# blink1mk3_005t6_5050_4l_usbc.net
KiCad netlist of a schematic drawn in EAGLE
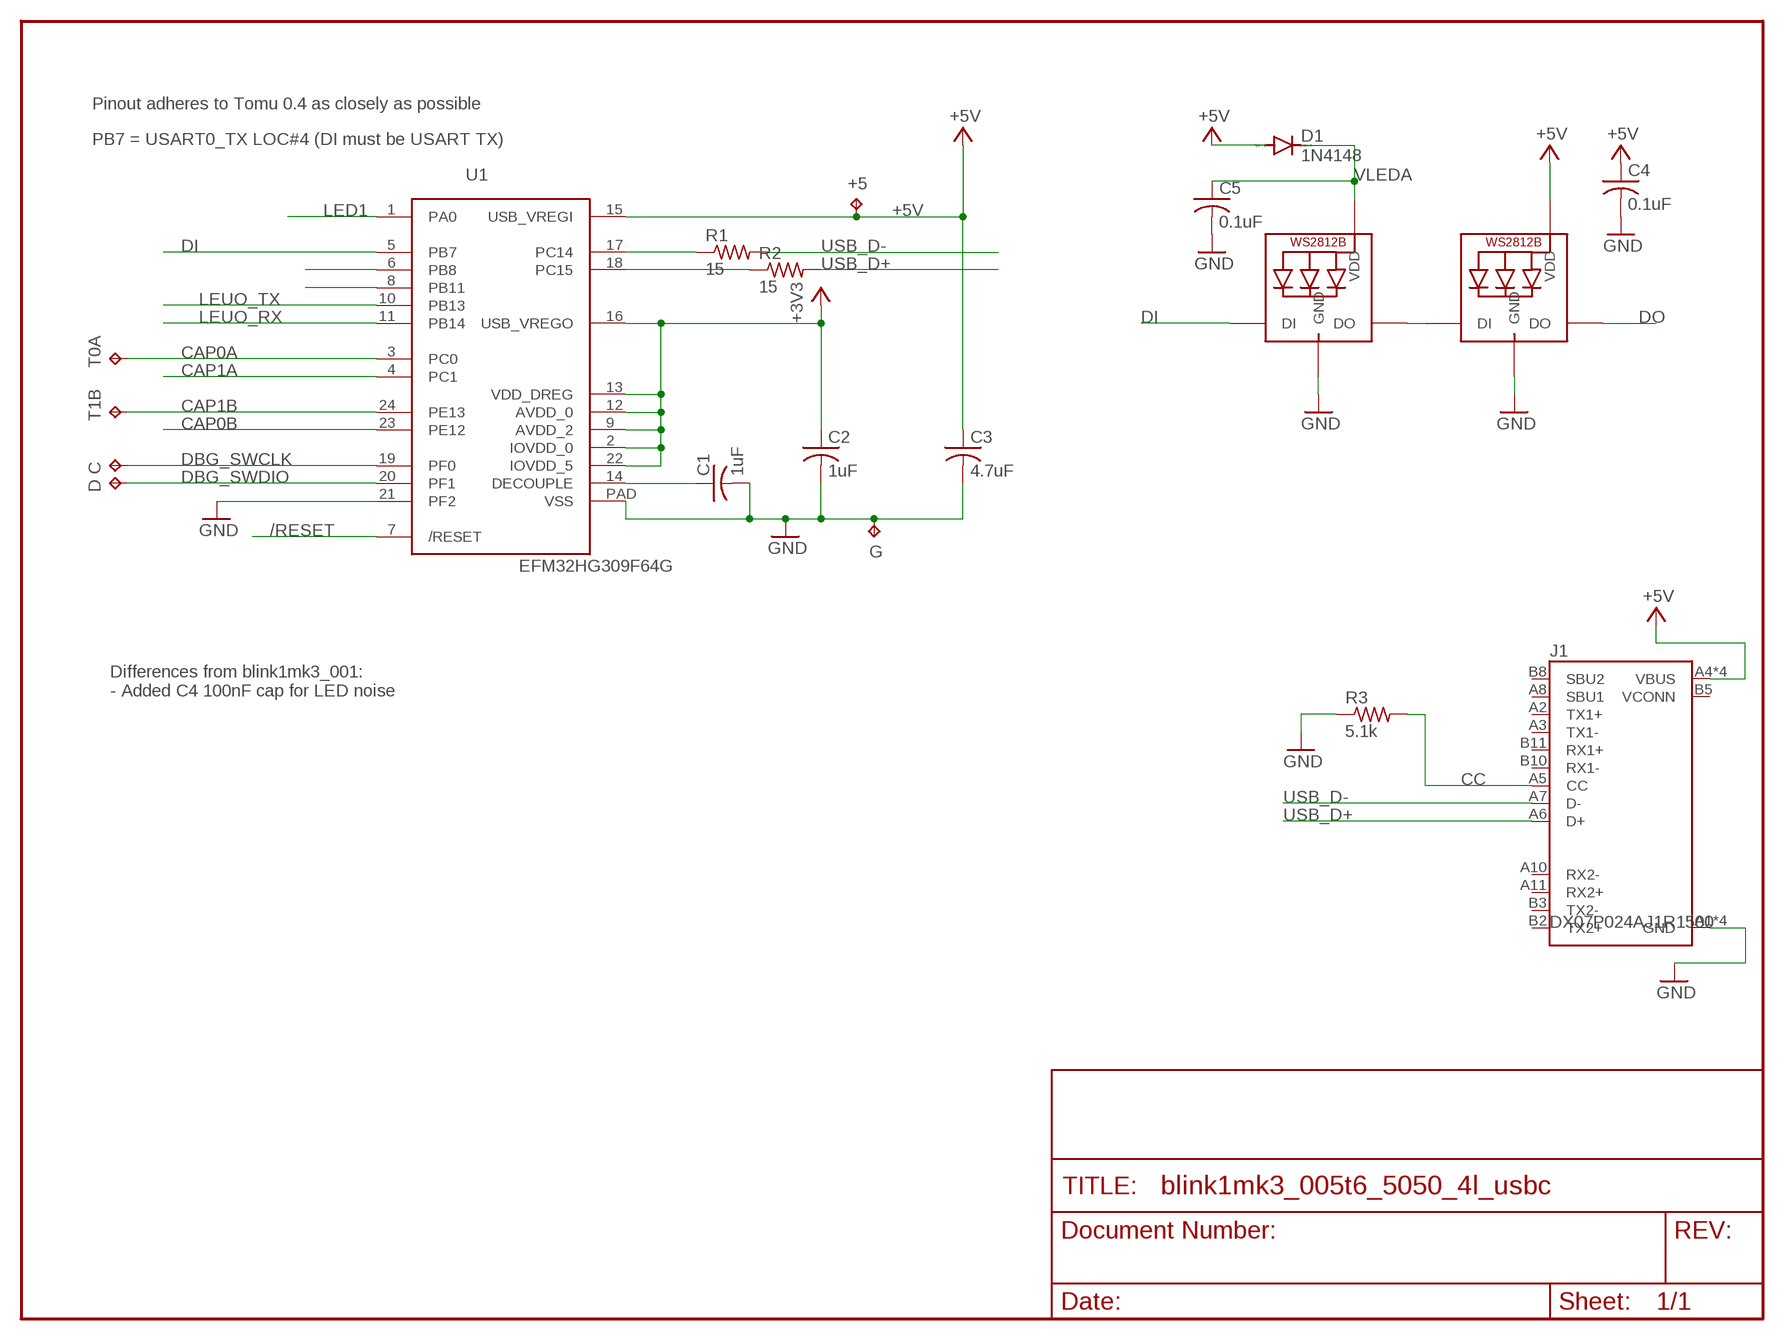
[diagram p0: schematic, sheet 1]

(export (version "E")
  (design (tool "Eeschema 10.0.6"))
  (components
    (comp (ref "+5")
      (value "TPTP10R")
      (footprint "eagle-import:TP10R")
      (libsource (lib "eagle-import") (part "TPTP10R"))
    )
    (comp (ref "C")
      (value "TPTP10R")
      (footprint "eagle-import:TP10R")
      (libsource (lib "eagle-import") (part "TPTP10R"))
    )
    (comp (ref "C1")
      (value "1uF")
      (footprint "eagle-import:C0402")
      (libsource (lib "eagle-import") (part "C-USC0402"))
    )
    (comp (ref "C2")
      (value "1uF")
      (footprint "eagle-import:C0402")
      (libsource (lib "eagle-import") (part "C-USC0402"))
    )
    (comp (ref "C3")
      (value "4.7uF")
      (footprint "eagle-import:C0402")
      (libsource (lib "eagle-import") (part "C-USC0402"))
    )
    (comp (ref "C4")
      (value "0.1uF")
      (footprint "eagle-import:C0402")
      (libsource (lib "eagle-import") (part "C-USC0402"))
    )
    (comp (ref "C5")
      (value "0.1uF")
      (footprint "eagle-import:C0402")
      (libsource (lib "eagle-import") (part "C-USC0402"))
    )
    (comp (ref "D")
      (value "TPTP10R")
      (footprint "eagle-import:TP10R")
      (libsource (lib "eagle-import") (part "TPTP10R"))
    )
    (comp (ref "D1")
      (value "1N4148")
      (footprint "eagle-import:SOD523")
      (libsource (lib "eagle-import") (part "DIODE-SOD523"))
    )
    (comp (ref "G")
      (value "TPTP10R")
      (footprint "eagle-import:TP10R")
      (libsource (lib "eagle-import") (part "TPTP10R"))
    )
    (comp (ref "J1")
      (value "DX07P024AJ1R1500")
      (footprint "eagle-import:JAE_DX07P024AJ1R1500")
      (fields (field (name "DIGI-KEY_PART_NUMBER") "670-2868-1-ND") (field (name "MF") "JAE Electronics"))
      (libsource (lib "eagle-import") (part "DX07P024AJ1R1500"))
    )
    (comp (ref "LED1")
      (value "SK6812MINI")
      (footprint "eagle-import:LED3535")
      (libsource (lib "eagle-import") (part "WS2812B3535"))
    )
    (comp (ref "LED2")
      (value "SK6812MINI")
      (footprint "eagle-import:LED3535")
      (libsource (lib "eagle-import") (part "WS2812B3535"))
    )
    (comp (ref "R1")
      (value "15")
      (footprint "eagle-import:R0402")
      (libsource (lib "eagle-import") (part "R-US_R0402"))
    )
    (comp (ref "R2")
      (value "15")
      (footprint "eagle-import:R0402")
      (libsource (lib "eagle-import") (part "R-US_R0402"))
    )
    (comp (ref "R3")
      (value "5.1k")
      (footprint "eagle-import:R0402")
      (libsource (lib "eagle-import") (part "R-US_R0402"))
    )
    (comp (ref "T0A")
      (value "TPTP15R")
      (footprint "eagle-import:TP15R")
      (libsource (lib "eagle-import") (part "TPTP15R"))
    )
    (comp (ref "T1B")
      (value "TPTP15R")
      (footprint "eagle-import:TP15R")
      (libsource (lib "eagle-import") (part "TPTP15R"))
    )
    (comp (ref "U1")
      (value "EFM32HG309F64G")
      (footprint "eagle-import:QFN24PAD")
      (libsource (lib "eagle-import") (part "EFM32HG309F64G"))
    )
  )
  (nets
    (net (code "1") (name "+3V3") (class "Default")
      (node (ref "C2") (pin "1") (pinfunction "1_1") (pintype "passive"))
      (node (ref "U1") (pin "12") (pinfunction "AVDD_0_12") (pintype "bidirectional"))
      (node (ref "U1") (pin "13") (pinfunction "VDD_DREG_13") (pintype "bidirectional"))
      (node (ref "U1") (pin "16") (pinfunction "USB_VREGO_16") (pintype "bidirectional"))
      (node (ref "U1") (pin "2") (pinfunction "IOVDD_0_2") (pintype "bidirectional"))
      (node (ref "U1") (pin "22") (pinfunction "IOVDD_5_22") (pintype "bidirectional"))
      (node (ref "U1") (pin "9") (pinfunction "AVDD_2_9") (pintype "bidirectional"))
    )
    (net (code "2") (name "+5V") (class "Default")
      (node (ref "+5") (pin "TP") (pinfunction "TP_TP") (pintype "input"))
      (node (ref "C3") (pin "1") (pinfunction "1_1") (pintype "passive"))
      (node (ref "C4") (pin "1") (pinfunction "1_1") (pintype "passive"))
      (node (ref "D1") (pin "A") (pinfunction "A_A") (pintype "passive"))
      (node (ref "J1") (pin "A4") (pinfunction "VBUS_A4") (pintype "power_in"))
      (node (ref "J1") (pin "A9") (pinfunction "VBUS_A9") (pintype "power_in"))
      (node (ref "J1") (pin "B4") (pinfunction "VBUS_B4") (pintype "power_in"))
      (node (ref "J1") (pin "B9") (pinfunction "VBUS_B9") (pintype "power_in"))
      (node (ref "LED2") (pin "2") (pinfunction "VDD_2") (pintype "power_in"))
      (node (ref "U1") (pin "15") (pinfunction "USB_VREGI_15") (pintype "bidirectional"))
    )
    (net (code "3") (name "/CAP0A") (class "Default")
      (node (ref "T0A") (pin "TP") (pinfunction "TP_TP") (pintype "input"))
      (node (ref "U1") (pin "3") (pinfunction "PC0_3") (pintype "bidirectional"))
    )
    (net (code "4") (name "/CAP0B") (class "Default")
      (node (ref "U1") (pin "23") (pinfunction "PE12_23") (pintype "bidirectional"))
    )
    (net (code "5") (name "/CAP1A") (class "Default")
      (node (ref "U1") (pin "4") (pinfunction "PC1_4") (pintype "bidirectional"))
    )
    (net (code "6") (name "/CAP1B") (class "Default")
      (node (ref "T1B") (pin "TP") (pinfunction "TP_TP") (pintype "input"))
      (node (ref "U1") (pin "24") (pinfunction "PE13_24") (pintype "bidirectional"))
    )
    (net (code "7") (name "/CC") (class "Default")
      (node (ref "J1") (pin "A5") (pinfunction "CC_A5") (pintype "bidirectional"))
      (node (ref "R3") (pin "2") (pinfunction "2_2") (pintype "passive"))
    )
    (net (code "8") (name "/DBG_SWCLK") (class "Default")
      (node (ref "C") (pin "TP") (pinfunction "TP_TP") (pintype "input"))
      (node (ref "U1") (pin "19") (pinfunction "PF0_19") (pintype "bidirectional"))
    )
    (net (code "9") (name "/DBG_SWDIO") (class "Default")
      (node (ref "D") (pin "TP") (pinfunction "TP_TP") (pintype "input"))
      (node (ref "U1") (pin "20") (pinfunction "PF1_20") (pintype "bidirectional"))
    )
    (net (code "10") (name "/DI") (class "Default")
      (node (ref "LED1") (pin "1") (pinfunction "DI_1") (pintype "input"))
      (node (ref "U1") (pin "5") (pinfunction "PB7_5") (pintype "bidirectional"))
    )
    (net (code "11") (name "/DO") (class "Default")
      (node (ref "LED2") (pin "3") (pinfunction "DO_3") (pintype "output"))
    )
    (net (code "12") (name "/LED1") (class "Default")
      (node (ref "U1") (pin "1") (pinfunction "PA0_1") (pintype "bidirectional"))
    )
    (net (code "13") (name "/LEUO_RX") (class "Default")
      (node (ref "U1") (pin "11") (pinfunction "PB14_11") (pintype "bidirectional"))
    )
    (net (code "14") (name "/LEUO_TX") (class "Default")
      (node (ref "U1") (pin "10") (pinfunction "PB13_10") (pintype "bidirectional"))
    )
    (net (code "15") (name "/USB_D+") (class "Default")
      (node (ref "J1") (pin "A6") (pinfunction "D+_A6") (pintype "bidirectional"))
      (node (ref "R2") (pin "2") (pinfunction "2_2") (pintype "passive"))
    )
    (net (code "16") (name "/USB_D-") (class "Default")
      (node (ref "J1") (pin "A7") (pinfunction "D-_A7") (pintype "bidirectional"))
      (node (ref "R1") (pin "2") (pinfunction "2_2") (pintype "passive"))
    )
    (net (code "17") (name "/VCONN") (class "Default")
      (node (ref "J1") (pin "B5") (pinfunction "VCONN_B5") (pintype "power_in"))
    )
    (net (code "18") (name "/VLEDA") (class "Default")
      (node (ref "C5") (pin "1") (pinfunction "1_1") (pintype "passive"))
      (node (ref "D1") (pin "C") (pinfunction "C_C") (pintype "passive"))
      (node (ref "LED1") (pin "2") (pinfunction "VDD_2") (pintype "power_in"))
    )
    (net (code "19") (name "/{slash}RESET") (class "Default")
      (node (ref "U1") (pin "7") (pinfunction "/RESET_7") (pintype "bidirectional"))
    )
    (net (code "20") (name "GND") (class "Default")
      (node (ref "C1") (pin "2") (pinfunction "2_2") (pintype "passive"))
      (node (ref "C2") (pin "2") (pinfunction "2_2") (pintype "passive"))
      (node (ref "C3") (pin "2") (pinfunction "2_2") (pintype "passive"))
      (node (ref "C4") (pin "2") (pinfunction "2_2") (pintype "passive"))
      (node (ref "C5") (pin "2") (pinfunction "2_2") (pintype "passive"))
      (node (ref "G") (pin "TP") (pinfunction "TP_TP") (pintype "input"))
      (node (ref "J1") (pin "A1") (pinfunction "GND_A1") (pintype "power_in"))
      (node (ref "J1") (pin "A12") (pinfunction "GND_A12") (pintype "power_in"))
      (node (ref "J1") (pin "B1") (pinfunction "GND_B1") (pintype "power_in"))
      (node (ref "J1") (pin "B12") (pinfunction "GND_B12") (pintype "power_in"))
      (node (ref "LED1") (pin "4") (pinfunction "GND_4") (pintype "power_in"))
      (node (ref "LED2") (pin "4") (pinfunction "GND_4") (pintype "power_in"))
      (node (ref "R3") (pin "1") (pinfunction "1_1") (pintype "passive"))
      (node (ref "U1") (pin "21") (pinfunction "PF2_21") (pintype "bidirectional"))
      (node (ref "U1") (pin "PAD") (pinfunction "VSS_PAD") (pintype "bidirectional"))
    )
    (net (code "21") (name "Net-(LED1-DO)") (class "Default")
      (node (ref "LED1") (pin "3") (pinfunction "DO_3") (pintype "output"))
      (node (ref "LED2") (pin "1") (pinfunction "DI_1") (pintype "input"))
    )
    (net (code "22") (name "Net-(U1-DECOUPLE)") (class "Default")
      (node (ref "C1") (pin "1") (pinfunction "1_1") (pintype "passive"))
      (node (ref "U1") (pin "14") (pinfunction "DECOUPLE_14") (pintype "bidirectional"))
    )
    (net (code "23") (name "Net-(U1-PC14)") (class "Default")
      (node (ref "R1") (pin "1") (pinfunction "1_1") (pintype "passive"))
      (node (ref "U1") (pin "17") (pinfunction "PC14_17") (pintype "bidirectional"))
    )
    (net (code "24") (name "Net-(U1-PC15)") (class "Default")
      (node (ref "R2") (pin "1") (pinfunction "1_1") (pintype "passive"))
      (node (ref "U1") (pin "18") (pinfunction "PC15_18") (pintype "bidirectional"))
    )
    (net (code "25") (name "unconnected-(J1-RX1+-PadB11)") (class "Default")
      (node (ref "J1") (pin "B11") (pinfunction "RX1+_B11") (pintype "bidirectional"))
    )
    (net (code "26") (name "unconnected-(J1-RX1--PadB10)") (class "Default")
      (node (ref "J1") (pin "B10") (pinfunction "RX1-_B10") (pintype "bidirectional"))
    )
    (net (code "27") (name "unconnected-(J1-RX2+-PadA11)") (class "Default")
      (node (ref "J1") (pin "A11") (pinfunction "RX2+_A11") (pintype "bidirectional"))
    )
    (net (code "28") (name "unconnected-(J1-RX2--PadA10)") (class "Default")
      (node (ref "J1") (pin "A10") (pinfunction "RX2-_A10") (pintype "bidirectional"))
    )
    (net (code "29") (name "unconnected-(J1-SBU1-PadA8)") (class "Default")
      (node (ref "J1") (pin "A8") (pinfunction "SBU1_A8") (pintype "bidirectional"))
    )
    (net (code "30") (name "unconnected-(J1-SBU2-PadB8)") (class "Default")
      (node (ref "J1") (pin "B8") (pinfunction "SBU2_B8") (pintype "bidirectional"))
    )
    (net (code "31") (name "unconnected-(J1-TX1+-PadA2)") (class "Default")
      (node (ref "J1") (pin "A2") (pinfunction "TX1+_A2") (pintype "bidirectional"))
    )
    (net (code "32") (name "unconnected-(J1-TX1--PadA3)") (class "Default")
      (node (ref "J1") (pin "A3") (pinfunction "TX1-_A3") (pintype "bidirectional"))
    )
    (net (code "33") (name "unconnected-(J1-TX2+-PadB2)") (class "Default")
      (node (ref "J1") (pin "B2") (pinfunction "TX2+_B2") (pintype "bidirectional"))
    )
    (net (code "34") (name "unconnected-(J1-TX2--PadB3)") (class "Default")
      (node (ref "J1") (pin "B3") (pinfunction "TX2-_B3") (pintype "bidirectional"))
    )
    (net (code "35") (name "unconnected-(U1-PB8-Pad6)") (class "Default")
      (node (ref "U1") (pin "6") (pinfunction "PB8_6") (pintype "bidirectional"))
    )
    (net (code "36") (name "unconnected-(U1-PB11-Pad8)") (class "Default")
      (node (ref "U1") (pin "8") (pinfunction "PB11_8") (pintype "bidirectional"))
    )
  )
)
